# uStatusBoard.net
KiCad netlist of a schematic drawn in EAGLE
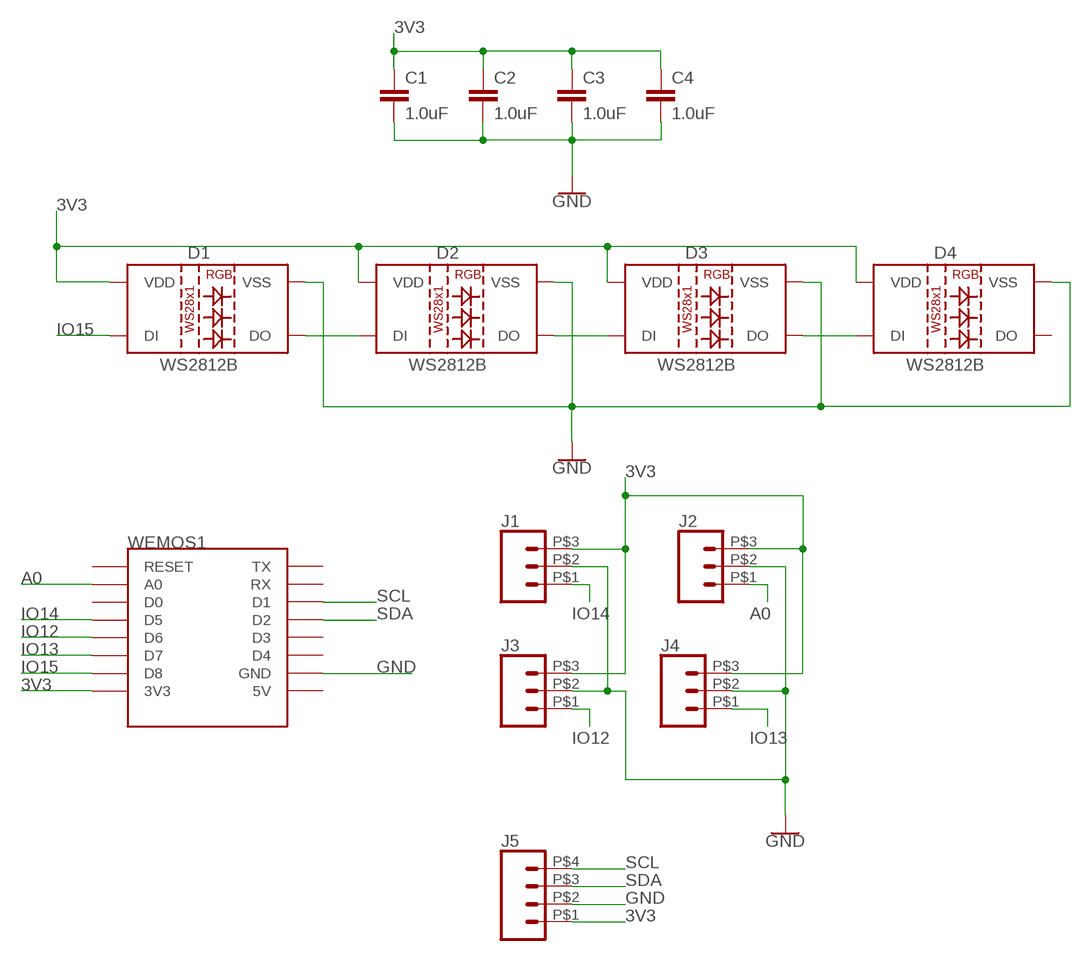
[diagram p0: schematic, sheet 1]

(export (version "E")
  (design (tool "Eeschema 10.0.6"))
  (components
    (comp (ref "C1")
      (value "1.0uF")
      (footprint "eagle-import:0805")
      (libsource (lib "eagle-import") (part "1.0UF-0805-25V-10%"))
    )
    (comp (ref "C2")
      (value "1.0uF")
      (footprint "eagle-import:0805")
      (libsource (lib "eagle-import") (part "1.0UF-0805-25V-10%"))
    )
    (comp (ref "C3")
      (value "1.0uF")
      (footprint "eagle-import:0805")
      (libsource (lib "eagle-import") (part "1.0UF-0805-25V-10%"))
    )
    (comp (ref "C4")
      (value "1.0uF")
      (footprint "eagle-import:0805")
      (libsource (lib "eagle-import") (part "1.0UF-0805-25V-10%"))
    )
    (comp (ref "D1")
      (value "WS2812B")
      (footprint "eagle-import:WS2812B")
      (libsource (lib "eagle-import") (part "WS2812B"))
    )
    (comp (ref "D2")
      (value "WS2812B")
      (footprint "eagle-import:WS2812B")
      (libsource (lib "eagle-import") (part "WS2812B"))
    )
    (comp (ref "D3")
      (value "WS2812B")
      (footprint "eagle-import:WS2812B")
      (libsource (lib "eagle-import") (part "WS2812B"))
    )
    (comp (ref "D4")
      (value "WS2812B")
      (footprint "eagle-import:WS2812B")
      (libsource (lib "eagle-import") (part "WS2812B"))
    )
    (comp (ref "J1")
      (value "CONN_031X03_SMD")
      (footprint "eagle-import:1X03_SMD")
      (libsource (lib "eagle-import") (part "CONN_031X03_SMD"))
    )
    (comp (ref "J2")
      (value "CONN_031X03_SMD")
      (footprint "eagle-import:1X03_SMD")
      (libsource (lib "eagle-import") (part "CONN_031X03_SMD"))
    )
    (comp (ref "J3")
      (value "CONN_031X03_SMD")
      (footprint "eagle-import:1X03_SMD")
      (libsource (lib "eagle-import") (part "CONN_031X03_SMD"))
    )
    (comp (ref "J4")
      (value "CONN_031X03_SMD")
      (footprint "eagle-import:1X03_SMD")
      (libsource (lib "eagle-import") (part "CONN_031X03_SMD"))
    )
    (comp (ref "J5")
      (value "CONN_041X04_SMD")
      (footprint "eagle-import:1X04_SMD")
      (libsource (lib "eagle-import") (part "CONN_041X04_SMD"))
    )
    (comp (ref "WEMOS1")
      (value "WEMOS-D1-MINIWEMOS_SMD")
      (footprint "eagle-import:WEMOS-SMD")
      (libsource (lib "eagle-import") (part "WEMOS-D1-MINIWEMOS_SMD"))
    )
  )
  (nets
    (net (code "1") (name "/3V3") (class "Default")
      (node (ref "C1") (pin "1") (pinfunction "1_1") (pintype "passive"))
      (node (ref "C2") (pin "1") (pinfunction "1_1") (pintype "passive"))
      (node (ref "C3") (pin "1") (pinfunction "1_1") (pintype "passive"))
      (node (ref "C4") (pin "1") (pinfunction "1_1") (pintype "passive"))
      (node (ref "D1") (pin "1") (pinfunction "VDD_1") (pintype "bidirectional"))
      (node (ref "D2") (pin "1") (pinfunction "VDD_1") (pintype "bidirectional"))
      (node (ref "D3") (pin "1") (pinfunction "VDD_1") (pintype "bidirectional"))
      (node (ref "D4") (pin "1") (pinfunction "VDD_1") (pintype "bidirectional"))
      (node (ref "J1") (pin "P$3") (pinfunction "3_P$3") (pintype "passive"))
      (node (ref "J2") (pin "P$3") (pinfunction "3_P$3") (pintype "passive"))
      (node (ref "J3") (pin "P$3") (pinfunction "3_P$3") (pintype "passive"))
      (node (ref "J4") (pin "P$3") (pinfunction "3_P$3") (pintype "passive"))
      (node (ref "J5") (pin "P$1") (pinfunction "1_P$1") (pintype "passive"))
      (node (ref "WEMOS1") (pin "3V3") (pinfunction "3V3_3V3") (pintype "bidirectional"))
    )
    (net (code "2") (name "/A0") (class "Default")
      (node (ref "J2") (pin "P$1") (pinfunction "1_P$1") (pintype "passive"))
      (node (ref "WEMOS1") (pin "A0") (pinfunction "A0_A0") (pintype "bidirectional"))
    )
    (net (code "3") (name "/IO12") (class "Default")
      (node (ref "J3") (pin "P$1") (pinfunction "1_P$1") (pintype "passive"))
      (node (ref "WEMOS1") (pin "D6") (pinfunction "D6_D6") (pintype "bidirectional"))
    )
    (net (code "4") (name "/IO13") (class "Default")
      (node (ref "J4") (pin "P$1") (pinfunction "1_P$1") (pintype "passive"))
      (node (ref "WEMOS1") (pin "D7") (pinfunction "D7_D7") (pintype "bidirectional"))
    )
    (net (code "5") (name "/IO14") (class "Default")
      (node (ref "J1") (pin "P$1") (pinfunction "1_P$1") (pintype "passive"))
      (node (ref "WEMOS1") (pin "D5") (pinfunction "D5_D5") (pintype "bidirectional"))
    )
    (net (code "6") (name "/IO15") (class "Default")
      (node (ref "D1") (pin "4") (pinfunction "DI_4") (pintype "bidirectional"))
      (node (ref "WEMOS1") (pin "D8") (pinfunction "D8_D8") (pintype "bidirectional"))
    )
    (net (code "7") (name "/SCL") (class "Default")
      (node (ref "J5") (pin "P$4") (pinfunction "4_P$4") (pintype "passive"))
      (node (ref "WEMOS1") (pin "D1") (pinfunction "D1_D1") (pintype "bidirectional"))
    )
    (net (code "8") (name "/SDA") (class "Default")
      (node (ref "J5") (pin "P$3") (pinfunction "3_P$3") (pintype "passive"))
      (node (ref "WEMOS1") (pin "D2") (pinfunction "D2_D2") (pintype "bidirectional"))
    )
    (net (code "9") (name "GND") (class "Default")
      (node (ref "C1") (pin "2") (pinfunction "2_2") (pintype "passive"))
      (node (ref "C2") (pin "2") (pinfunction "2_2") (pintype "passive"))
      (node (ref "C3") (pin "2") (pinfunction "2_2") (pintype "passive"))
      (node (ref "C4") (pin "2") (pinfunction "2_2") (pintype "passive"))
      (node (ref "D1") (pin "3") (pinfunction "VSS_3") (pintype "bidirectional"))
      (node (ref "D2") (pin "3") (pinfunction "VSS_3") (pintype "bidirectional"))
      (node (ref "D3") (pin "3") (pinfunction "VSS_3") (pintype "bidirectional"))
      (node (ref "D4") (pin "3") (pinfunction "VSS_3") (pintype "bidirectional"))
      (node (ref "J1") (pin "P$2") (pinfunction "2_P$2") (pintype "passive"))
      (node (ref "J2") (pin "P$2") (pinfunction "2_P$2") (pintype "passive"))
      (node (ref "J3") (pin "P$2") (pinfunction "2_P$2") (pintype "passive"))
      (node (ref "J4") (pin "P$2") (pinfunction "2_P$2") (pintype "passive"))
      (node (ref "J5") (pin "P$2") (pinfunction "2_P$2") (pintype "passive"))
      (node (ref "WEMOS1") (pin "GND") (pinfunction "GND_GND") (pintype "bidirectional"))
    )
    (net (code "10") (name "Net-(D1-DO)") (class "Default")
      (node (ref "D1") (pin "2") (pinfunction "DO_2") (pintype "bidirectional"))
      (node (ref "D2") (pin "4") (pinfunction "DI_4") (pintype "bidirectional"))
    )
    (net (code "11") (name "Net-(D2-DO)") (class "Default")
      (node (ref "D2") (pin "2") (pinfunction "DO_2") (pintype "bidirectional"))
      (node (ref "D3") (pin "4") (pinfunction "DI_4") (pintype "bidirectional"))
    )
    (net (code "12") (name "Net-(D3-DO)") (class "Default")
      (node (ref "D3") (pin "2") (pinfunction "DO_2") (pintype "bidirectional"))
      (node (ref "D4") (pin "4") (pinfunction "DI_4") (pintype "bidirectional"))
    )
    (net (code "13") (name "unconnected-(D4-DO-Pad2)") (class "Default")
      (node (ref "D4") (pin "2") (pinfunction "DO_2") (pintype "bidirectional"))
    )
    (net (code "14") (name "unconnected-(WEMOS1-Pad5V)") (class "Default")
      (node (ref "WEMOS1") (pin "5V") (pinfunction "5V_5V") (pintype "bidirectional"))
    )
    (net (code "15") (name "unconnected-(WEMOS1-PadD0)") (class "Default")
      (node (ref "WEMOS1") (pin "D0") (pinfunction "D0_D0") (pintype "bidirectional"))
    )
    (net (code "16") (name "unconnected-(WEMOS1-PadD3)") (class "Default")
      (node (ref "WEMOS1") (pin "D3") (pinfunction "D3_D3") (pintype "bidirectional"))
    )
    (net (code "17") (name "unconnected-(WEMOS1-PadD4)") (class "Default")
      (node (ref "WEMOS1") (pin "D4") (pinfunction "D4_D4") (pintype "bidirectional"))
    )
    (net (code "18") (name "unconnected-(WEMOS1-PadRESET)") (class "Default")
      (node (ref "WEMOS1") (pin "RESET") (pinfunction "RESET_RESET") (pintype "bidirectional"))
    )
    (net (code "19") (name "unconnected-(WEMOS1-PadRX)") (class "Default")
      (node (ref "WEMOS1") (pin "RX") (pinfunction "RX_RX") (pintype "bidirectional"))
    )
    (net (code "20") (name "unconnected-(WEMOS1-PadTX)") (class "Default")
      (node (ref "WEMOS1") (pin "TX") (pinfunction "TX_TX") (pintype "bidirectional"))
    )
  )
)
